# nRF52810_Beacon.net
KiCad netlist of a schematic drawn in EAGLE
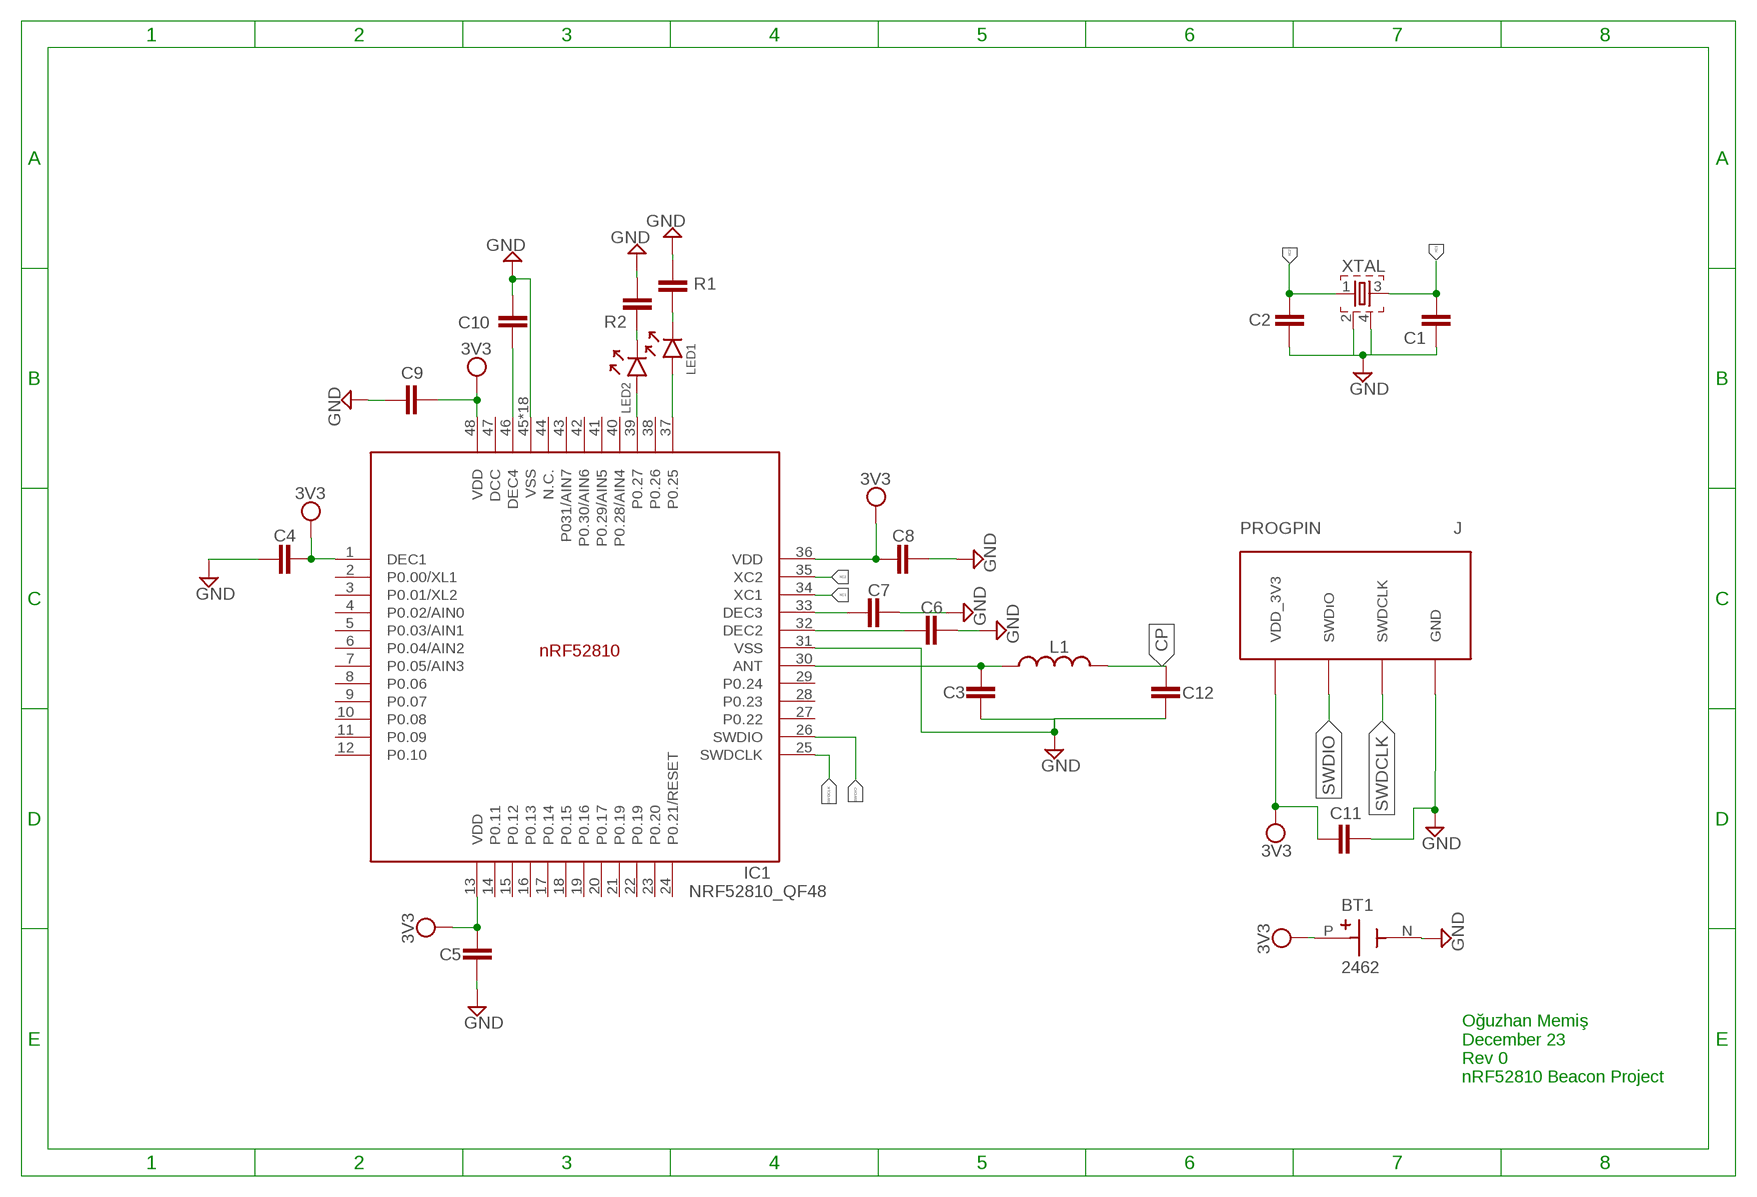
[diagram p0: schematic, sheet 1]

(export (version "E")
  (design (tool "Eeschema 10.0.6"))
  (components
    (comp (ref "BT1")
      (value "2462")
      (footprint "eagle-import:BAT_2462")
      (fields (field (name "MF") "Keystone"))
      (libsource (lib "eagle-import") (part "2462"))
    )
    (comp (ref "C1")
      (value "12pF")
      (footprint "eagle-import:RESC0402_N")
      (libsource (lib "eagle-import") (part "CAPACITOR_0402_N"))
    )
    (comp (ref "C2")
      (value "12pF")
      (footprint "eagle-import:RESC0402_N")
      (libsource (lib "eagle-import") (part "CAPACITOR_0402_N"))
    )
    (comp (ref "C3")
      (value "0.8pF")
      (footprint "eagle-import:RESC0402_N")
      (libsource (lib "eagle-import") (part "CAPACITOR_0402_N"))
    )
    (comp (ref "C4")
      (value "100nF")
      (footprint "eagle-import:RESC0402_N")
      (libsource (lib "eagle-import") (part "CAPACITOR_0402_N"))
    )
    (comp (ref "C5")
      (value "100nF")
      (footprint "eagle-import:RESC0402_N")
      (libsource (lib "eagle-import") (part "CAPACITOR_0402_N"))
    )
    (comp (ref "C6")
      (value "100pF")
      (footprint "eagle-import:RESC0402_N")
      (libsource (lib "eagle-import") (part "CAPACITOR_0402_N"))
    )
    (comp (ref "C7")
      (value "100pF")
      (footprint "eagle-import:RESC0402_N")
      (libsource (lib "eagle-import") (part "CAPACITOR_0402_N"))
    )
    (comp (ref "C8")
      (value "100nF")
      (footprint "eagle-import:RESC0402_N")
      (libsource (lib "eagle-import") (part "CAPACITOR_0402_N"))
    )
    (comp (ref "C9")
      (value "4.7uF")
      (footprint "eagle-import:RESC0603_N")
      (libsource (lib "eagle-import") (part "CAPACITOR_0603_N"))
    )
    (comp (ref "C10")
      (value "1uF")
      (footprint "eagle-import:RESC0603_N")
      (libsource (lib "eagle-import") (part "CAPACITOR_0603_N"))
    )
    (comp (ref "C11")
      (value "100nF")
      (footprint "eagle-import:RESC0603_N")
      (libsource (lib "eagle-import") (part "CAPACITOR_0603_N"))
    )
    (comp (ref "C12")
      (value "1.2pF")
      (footprint "eagle-import:RESC0402_N")
      (libsource (lib "eagle-import") (part "CAPACITOR_0402_N"))
    )
    (comp (ref "IC1")
      (value "NRF52810_QF48")
      (footprint "eagle-import:QFN40P600X600X90-48_N")
      (libsource (lib "eagle-import") (part "NRF52810_QF48"))
    )
    (comp (ref "L1")
      (value "3.9nF")
      (footprint "eagle-import:RESC0402_N")
      (libsource (lib "eagle-import") (part "INDUCTOR_0402_N"))
    )
    (comp (ref "LED1")
      (value "LED")
      (footprint "eagle-import:DIOC0603_N")
      (libsource (lib "eagle-import") (part "LED"))
    )
    (comp (ref "LED2")
      (value "LED")
      (footprint "eagle-import:DIOC0603_N")
      (libsource (lib "eagle-import") (part "LED"))
    )
    (comp (ref "R1")
      (value "560R")
      (footprint "eagle-import:RESC0603_N")
      (libsource (lib "eagle-import") (part "CAPACITOR_0603_N"))
    )
    (comp (ref "R2")
      (value "560R")
      (footprint "eagle-import:RESC0603_N")
      (libsource (lib "eagle-import") (part "CAPACITOR_0603_N"))
    )
    (comp (ref "U$1")
      (value "PROGPIN4*2.54")
      (footprint "eagle-import:PROGPIN")
      (libsource (lib "eagle-import") (part "PROGPIN42.54"))
    )
    (comp (ref "XTAL")
      (value "32MHz SMD2016")
      (footprint "eagle-import:BT-XTAL_2016_N")
      (libsource (lib "eagle-import") (part "XTAL_32MHZ"))
    )
  )
  (nets
    (net (code "1") (name "CP") (class "Default")
      (node (ref "C12") (pin "1") (pinfunction "1_1") (pintype "passive"))
      (node (ref "L1") (pin "2") (pinfunction "2_2") (pintype "passive"))
    )
    (net (code "2") (name "GND") (class "Default")
      (node (ref "BT1") (pin "N") (pinfunction "NEG_N") (pintype "passive"))
      (node (ref "C1") (pin "1") (pinfunction "1_1") (pintype "passive"))
      (node (ref "C10") (pin "2") (pinfunction "2_2") (pintype "passive"))
      (node (ref "C11") (pin "2") (pinfunction "2_2") (pintype "passive"))
      (node (ref "C12") (pin "2") (pinfunction "2_2") (pintype "passive"))
      (node (ref "C2") (pin "1") (pinfunction "1_1") (pintype "passive"))
      (node (ref "C3") (pin "2") (pinfunction "2_2") (pintype "passive"))
      (node (ref "C4") (pin "1") (pinfunction "1_1") (pintype "passive"))
      (node (ref "C5") (pin "2") (pinfunction "2_2") (pintype "passive"))
      (node (ref "C6") (pin "2") (pinfunction "2_2") (pintype "passive"))
      (node (ref "C7") (pin "2") (pinfunction "2_2") (pintype "passive"))
      (node (ref "C8") (pin "2") (pinfunction "2_2") (pintype "passive"))
      (node (ref "C9") (pin "1") (pinfunction "1_1") (pintype "passive"))
      (node (ref "IC1") (pin "31") (pinfunction "VSS_31") (pintype "bidirectional"))
      (node (ref "IC1") (pin "45") (pinfunction "VSS_45") (pintype "bidirectional"))
      (node (ref "IC1") (pin "PAD") (pinfunction "VSS_PAD") (pintype "bidirectional"))
      (node (ref "IC1") (pin "PAD@VIA01") (pinfunction "VSS_PAD@VIA01") (pintype "bidirectional"))
      (node (ref "IC1") (pin "PAD@VIA02") (pinfunction "VSS_PAD@VIA02") (pintype "bidirectional"))
      (node (ref "IC1") (pin "PAD@VIA03") (pinfunction "VSS_PAD@VIA03") (pintype "bidirectional"))
      (node (ref "IC1") (pin "PAD@VIA04") (pinfunction "VSS_PAD@VIA04") (pintype "bidirectional"))
      (node (ref "IC1") (pin "PAD@VIA05") (pinfunction "VSS_PAD@VIA05") (pintype "bidirectional"))
      (node (ref "IC1") (pin "PAD@VIA06") (pinfunction "VSS_PAD@VIA06") (pintype "bidirectional"))
      (node (ref "IC1") (pin "PAD@VIA07") (pinfunction "VSS_PAD@VIA07") (pintype "bidirectional"))
      (node (ref "IC1") (pin "PAD@VIA08") (pinfunction "VSS_PAD@VIA08") (pintype "bidirectional"))
      (node (ref "IC1") (pin "PAD@VIA09") (pinfunction "VSS_PAD@VIA09") (pintype "bidirectional"))
      (node (ref "IC1") (pin "PAD@VIA10") (pinfunction "VSS_PAD@VIA10") (pintype "bidirectional"))
      (node (ref "IC1") (pin "PAD@VIA11") (pinfunction "VSS_PAD@VIA11") (pintype "bidirectional"))
      (node (ref "IC1") (pin "PAD@VIA12") (pinfunction "VSS_PAD@VIA12") (pintype "bidirectional"))
      (node (ref "IC1") (pin "PAD@VIA13") (pinfunction "VSS_PAD@VIA13") (pintype "bidirectional"))
      (node (ref "IC1") (pin "PAD@VIA14") (pinfunction "VSS_PAD@VIA14") (pintype "bidirectional"))
      (node (ref "IC1") (pin "PAD@VIA15") (pinfunction "VSS_PAD@VIA15") (pintype "bidirectional"))
      (node (ref "IC1") (pin "PAD@VIA16") (pinfunction "VSS_PAD@VIA16") (pintype "bidirectional"))
      (node (ref "R1") (pin "2") (pinfunction "2_2") (pintype "passive"))
      (node (ref "R2") (pin "2") (pinfunction "2_2") (pintype "passive"))
      (node (ref "U$1") (pin "GND") (pinfunction "GND_GND") (pintype "bidirectional"))
      (node (ref "XTAL") (pin "2") (pinfunction "2_2") (pintype "passive"))
      (node (ref "XTAL") (pin "4") (pinfunction "4_4") (pintype "passive"))
    )
    (net (code "3") (name "Net-(IC1-ANT)") (class "Default")
      (node (ref "C3") (pin "1") (pinfunction "1_1") (pintype "passive"))
      (node (ref "IC1") (pin "30") (pinfunction "ANT_30") (pintype "bidirectional"))
      (node (ref "L1") (pin "1") (pinfunction "1_1") (pintype "passive"))
    )
    (net (code "4") (name "Net-(IC1-DEC2)") (class "Default")
      (node (ref "C6") (pin "1") (pinfunction "1_1") (pintype "passive"))
      (node (ref "IC1") (pin "32") (pinfunction "DEC2_32") (pintype "bidirectional"))
    )
    (net (code "5") (name "Net-(IC1-DEC3)") (class "Default")
      (node (ref "C7") (pin "1") (pinfunction "1_1") (pintype "passive"))
      (node (ref "IC1") (pin "33") (pinfunction "DEC3_33") (pintype "bidirectional"))
    )
    (net (code "6") (name "Net-(IC1-DEC4)") (class "Default")
      (node (ref "C10") (pin "1") (pinfunction "1_1") (pintype "passive"))
      (node (ref "IC1") (pin "46") (pinfunction "DEC4_46") (pintype "bidirectional"))
    )
    (net (code "7") (name "Net-(IC1-P0.25)") (class "Default")
      (node (ref "IC1") (pin "37") (pinfunction "P0.25_37") (pintype "bidirectional"))
      (node (ref "LED1") (pin "2") (pinfunction "A_2") (pintype "bidirectional"))
    )
    (net (code "8") (name "Net-(IC1-P0.27)") (class "Default")
      (node (ref "IC1") (pin "39") (pinfunction "P0.27_39") (pintype "bidirectional"))
      (node (ref "LED2") (pin "2") (pinfunction "A_2") (pintype "bidirectional"))
    )
    (net (code "9") (name "Net-(LED1-C)") (class "Default")
      (node (ref "LED1") (pin "1") (pinfunction "C_1") (pintype "bidirectional"))
      (node (ref "R1") (pin "1") (pinfunction "1_1") (pintype "passive"))
    )
    (net (code "10") (name "Net-(LED2-C)") (class "Default")
      (node (ref "LED2") (pin "1") (pinfunction "C_1") (pintype "bidirectional"))
      (node (ref "R2") (pin "1") (pinfunction "1_1") (pintype "passive"))
    )
    (net (code "11") (name "SWDCLK") (class "Default")
      (node (ref "IC1") (pin "25") (pinfunction "SWDCLK_25") (pintype "bidirectional"))
      (node (ref "U$1") (pin "SWDCLK") (pinfunction "SWDCLK_SWDCLK") (pintype "bidirectional"))
    )
    (net (code "12") (name "SWDIO") (class "Default")
      (node (ref "IC1") (pin "26") (pinfunction "SWDIO_26") (pintype "bidirectional"))
      (node (ref "U$1") (pin "SWDIO") (pinfunction "SWDıO_SWDIO") (pintype "bidirectional"))
    )
    (net (code "13") (name "VDD") (class "Default")
      (node (ref "BT1") (pin "P") (pinfunction "POS_P") (pintype "passive"))
      (node (ref "C11") (pin "1") (pinfunction "1_1") (pintype "passive"))
      (node (ref "C4") (pin "2") (pinfunction "2_2") (pintype "passive"))
      (node (ref "C5") (pin "1") (pinfunction "1_1") (pintype "passive"))
      (node (ref "C8") (pin "1") (pinfunction "1_1") (pintype "passive"))
      (node (ref "C9") (pin "2") (pinfunction "2_2") (pintype "passive"))
      (node (ref "IC1") (pin "1") (pinfunction "DEC1_1") (pintype "bidirectional"))
      (node (ref "IC1") (pin "13") (pinfunction "VDD_13") (pintype "bidirectional"))
      (node (ref "IC1") (pin "36") (pinfunction "VDD_36") (pintype "bidirectional"))
      (node (ref "IC1") (pin "48") (pinfunction "VDD_48") (pintype "bidirectional"))
      (node (ref "U$1") (pin "VDD_3V3") (pinfunction "VDD_3V3_VDD_3V3") (pintype "bidirectional"))
    )
    (net (code "14") (name "XC1") (class "Default")
      (node (ref "C1") (pin "2") (pinfunction "2_2") (pintype "passive"))
      (node (ref "IC1") (pin "34") (pinfunction "XC1_34") (pintype "bidirectional"))
      (node (ref "XTAL") (pin "3") (pinfunction "3_3") (pintype "passive"))
    )
    (net (code "15") (name "XC2") (class "Default")
      (node (ref "C2") (pin "2") (pinfunction "2_2") (pintype "passive"))
      (node (ref "IC1") (pin "35") (pinfunction "XC2_35") (pintype "bidirectional"))
      (node (ref "XTAL") (pin "1") (pinfunction "1_1") (pintype "passive"))
    )
    (net (code "16") (name "unconnected-(IC1-DCC-Pad47)") (class "Default")
      (node (ref "IC1") (pin "47") (pinfunction "DCC_47") (pintype "bidirectional"))
    )
    (net (code "17") (name "unconnected-(IC1-N.C.-Pad44)") (class "Default")
      (node (ref "IC1") (pin "44") (pinfunction "N.C._44") (pintype "bidirectional"))
    )
    (net (code "18") (name "unconnected-(IC1-P0.00{slash}XL1-Pad2)") (class "Default")
      (node (ref "IC1") (pin "2") (pinfunction "P0.00/XL1_2") (pintype "bidirectional"))
    )
    (net (code "19") (name "unconnected-(IC1-P0.01{slash}XL2-Pad3)") (class "Default")
      (node (ref "IC1") (pin "3") (pinfunction "P0.01/XL2_3") (pintype "bidirectional"))
    )
    (net (code "20") (name "unconnected-(IC1-P0.02{slash}AIN0-Pad4)") (class "Default")
      (node (ref "IC1") (pin "4") (pinfunction "P0.02/AIN0_4") (pintype "bidirectional"))
    )
    (net (code "21") (name "unconnected-(IC1-P0.03{slash}AIN1-Pad5)") (class "Default")
      (node (ref "IC1") (pin "5") (pinfunction "P0.03/AIN1_5") (pintype "bidirectional"))
    )
    (net (code "22") (name "unconnected-(IC1-P0.04{slash}AIN2-Pad6)") (class "Default")
      (node (ref "IC1") (pin "6") (pinfunction "P0.04/AIN2_6") (pintype "bidirectional"))
    )
    (net (code "23") (name "unconnected-(IC1-P0.05{slash}AIN3-Pad7)") (class "Default")
      (node (ref "IC1") (pin "7") (pinfunction "P0.05/AIN3_7") (pintype "bidirectional"))
    )
    (net (code "24") (name "unconnected-(IC1-P0.06-Pad8)") (class "Default")
      (node (ref "IC1") (pin "8") (pinfunction "P0.06_8") (pintype "bidirectional"))
    )
    (net (code "25") (name "unconnected-(IC1-P0.07-Pad9)") (class "Default")
      (node (ref "IC1") (pin "9") (pinfunction "P0.07_9") (pintype "bidirectional"))
    )
    (net (code "26") (name "unconnected-(IC1-P0.08-Pad10)") (class "Default")
      (node (ref "IC1") (pin "10") (pinfunction "P0.08_10") (pintype "bidirectional"))
    )
    (net (code "27") (name "unconnected-(IC1-P0.09-Pad11)") (class "Default")
      (node (ref "IC1") (pin "11") (pinfunction "P0.09_11") (pintype "bidirectional"))
    )
    (net (code "28") (name "unconnected-(IC1-P0.10-Pad12)") (class "Default")
      (node (ref "IC1") (pin "12") (pinfunction "P0.10_12") (pintype "bidirectional"))
    )
    (net (code "29") (name "unconnected-(IC1-P0.11-Pad14)") (class "Default")
      (node (ref "IC1") (pin "14") (pinfunction "P0.11_14") (pintype "bidirectional"))
    )
    (net (code "30") (name "unconnected-(IC1-P0.12-Pad15)") (class "Default")
      (node (ref "IC1") (pin "15") (pinfunction "P0.12_15") (pintype "bidirectional"))
    )
    (net (code "31") (name "unconnected-(IC1-P0.13-Pad16)") (class "Default")
      (node (ref "IC1") (pin "16") (pinfunction "P0.13_16") (pintype "bidirectional"))
    )
    (net (code "32") (name "unconnected-(IC1-P0.14-Pad17)") (class "Default")
      (node (ref "IC1") (pin "17") (pinfunction "P0.14_17") (pintype "bidirectional"))
    )
    (net (code "33") (name "unconnected-(IC1-P0.15-Pad18)") (class "Default")
      (node (ref "IC1") (pin "18") (pinfunction "P0.15_18") (pintype "bidirectional"))
    )
    (net (code "34") (name "unconnected-(IC1-P0.16-Pad19)") (class "Default")
      (node (ref "IC1") (pin "19") (pinfunction "P0.16_19") (pintype "bidirectional"))
    )
    (net (code "35") (name "unconnected-(IC1-P0.17-Pad20)") (class "Default")
      (node (ref "IC1") (pin "20") (pinfunction "P0.17_20") (pintype "bidirectional"))
    )
    (net (code "36") (name "unconnected-(IC1-P0.19-Pad21)") (class "Default")
      (node (ref "IC1") (pin "21") (pinfunction "P0.19_21") (pintype "bidirectional"))
    )
    (net (code "37") (name "unconnected-(IC1-P0.19-Pad22)") (class "Default")
      (node (ref "IC1") (pin "22") (pinfunction "P0.19_22") (pintype "bidirectional"))
    )
    (net (code "38") (name "unconnected-(IC1-P0.20-Pad23)") (class "Default")
      (node (ref "IC1") (pin "23") (pinfunction "P0.20_23") (pintype "bidirectional"))
    )
    (net (code "39") (name "unconnected-(IC1-P0.21{slash}RESET-Pad24)") (class "Default")
      (node (ref "IC1") (pin "24") (pinfunction "P0.21/RESET_24") (pintype "bidirectional"))
    )
    (net (code "40") (name "unconnected-(IC1-P0.22-Pad27)") (class "Default")
      (node (ref "IC1") (pin "27") (pinfunction "P0.22_27") (pintype "bidirectional"))
    )
    (net (code "41") (name "unconnected-(IC1-P0.23-Pad28)") (class "Default")
      (node (ref "IC1") (pin "28") (pinfunction "P0.23_28") (pintype "bidirectional"))
    )
    (net (code "42") (name "unconnected-(IC1-P0.24-Pad29)") (class "Default")
      (node (ref "IC1") (pin "29") (pinfunction "P0.24_29") (pintype "bidirectional"))
    )
    (net (code "43") (name "unconnected-(IC1-P0.26-Pad38)") (class "Default")
      (node (ref "IC1") (pin "38") (pinfunction "P0.26_38") (pintype "bidirectional"))
    )
    (net (code "44") (name "unconnected-(IC1-P0.28{slash}AIN4-Pad40)") (class "Default")
      (node (ref "IC1") (pin "40") (pinfunction "P0.28/AIN4_40") (pintype "bidirectional"))
    )
    (net (code "45") (name "unconnected-(IC1-P0.29{slash}AIN5-Pad41)") (class "Default")
      (node (ref "IC1") (pin "41") (pinfunction "P0.29/AIN5_41") (pintype "bidirectional"))
    )
    (net (code "46") (name "unconnected-(IC1-P0.30{slash}AIN6-Pad42)") (class "Default")
      (node (ref "IC1") (pin "42") (pinfunction "P0.30/AIN6_42") (pintype "bidirectional"))
    )
    (net (code "47") (name "unconnected-(IC1-P031{slash}AIN7-Pad43)") (class "Default")
      (node (ref "IC1") (pin "43") (pinfunction "P031/AIN7_43") (pintype "bidirectional"))
    )
  )
)
